# board.net
KiCad netlist of a schematic drawn in EAGLE
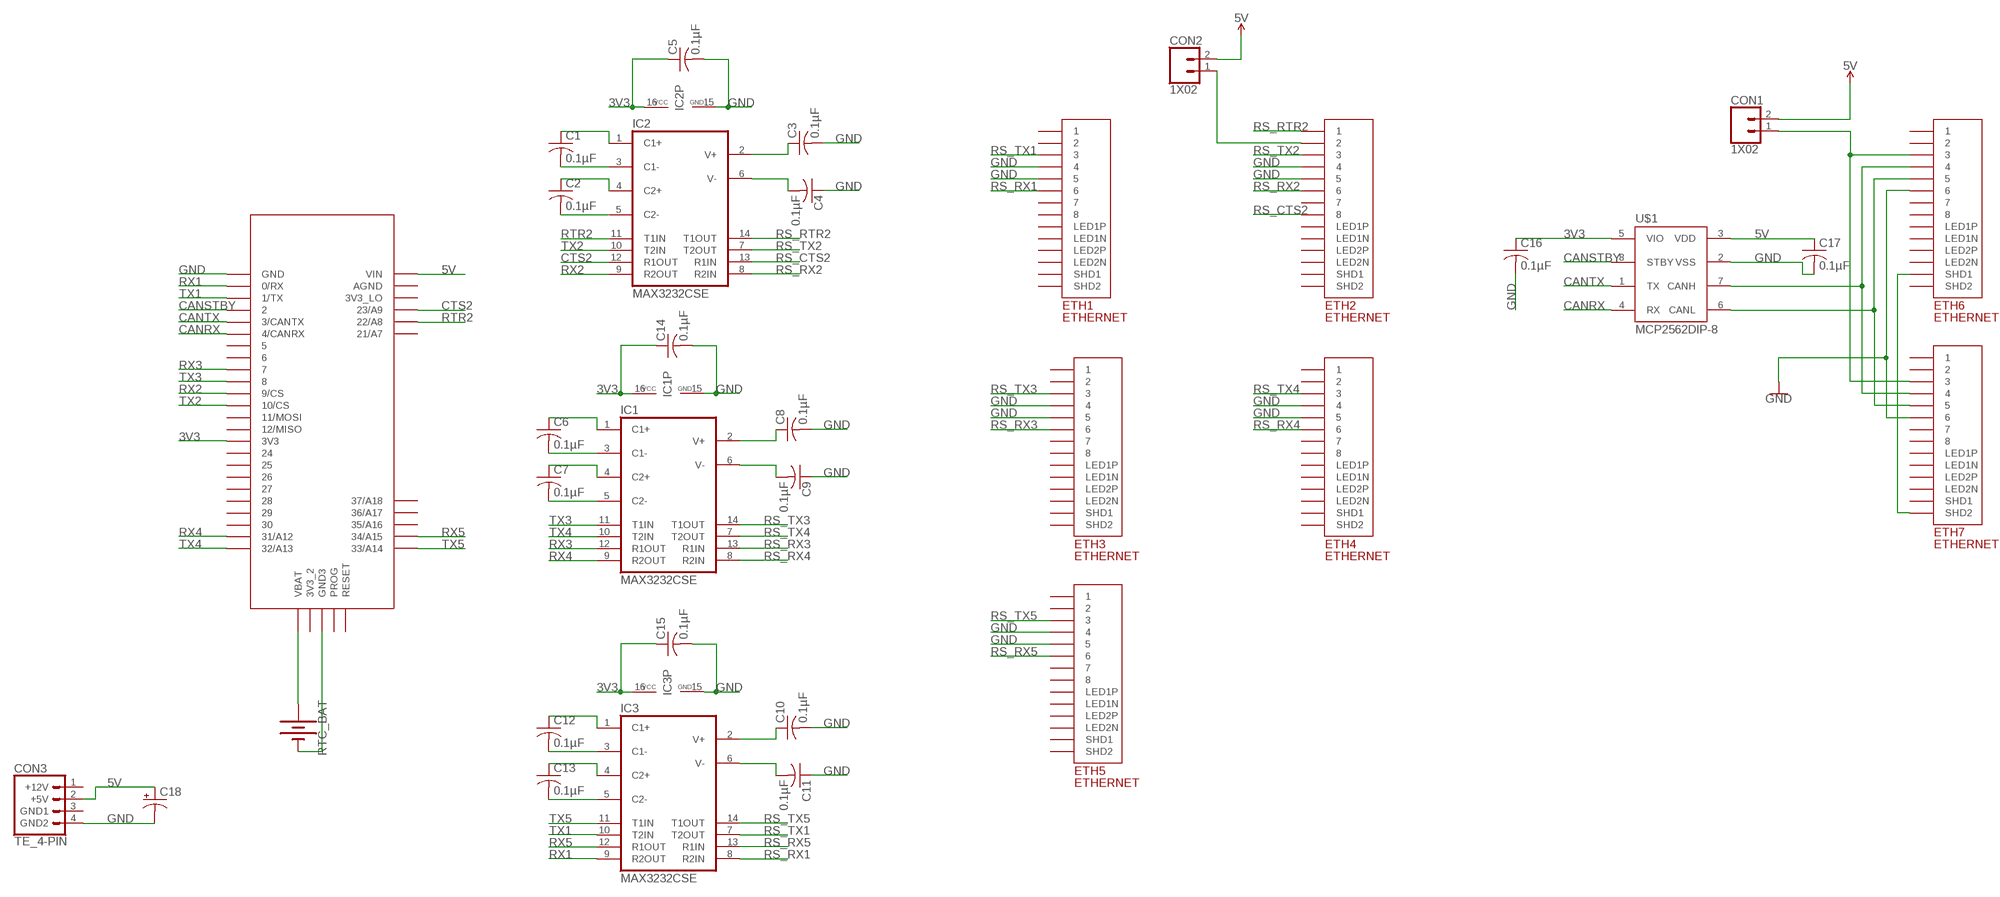
[diagram p0: schematic, sheet 1]

(export (version "E")
  (design (tool "Eeschema 10.0.6"))
  (components
    (comp (ref "C1")
      (value "0.1µF")
      (footprint "eagle-import:C0805")
      (libsource (lib "eagle-import") (part "C-USC0805"))
    )
    (comp (ref "C2")
      (value "0.1µF")
      (footprint "eagle-import:C0805")
      (libsource (lib "eagle-import") (part "C-USC0805"))
    )
    (comp (ref "C3")
      (value "0.1µF")
      (footprint "eagle-import:C0805")
      (libsource (lib "eagle-import") (part "C-USC0805"))
    )
    (comp (ref "C4")
      (value "0.1µF")
      (footprint "eagle-import:C0805")
      (libsource (lib "eagle-import") (part "C-USC0805"))
    )
    (comp (ref "C5")
      (value "0.1µF")
      (footprint "eagle-import:C0805")
      (libsource (lib "eagle-import") (part "C-USC0805"))
    )
    (comp (ref "C6")
      (value "0.1µF")
      (footprint "eagle-import:C0805")
      (libsource (lib "eagle-import") (part "C-USC0805"))
    )
    (comp (ref "C7")
      (value "0.1µF")
      (footprint "eagle-import:C0805")
      (libsource (lib "eagle-import") (part "C-USC0805"))
    )
    (comp (ref "C8")
      (value "0.1µF")
      (footprint "eagle-import:C0805")
      (libsource (lib "eagle-import") (part "C-USC0805"))
    )
    (comp (ref "C9")
      (value "0.1µF")
      (footprint "eagle-import:C0805")
      (libsource (lib "eagle-import") (part "C-USC0805"))
    )
    (comp (ref "C10")
      (value "0.1µF")
      (footprint "eagle-import:C0805")
      (libsource (lib "eagle-import") (part "C-USC0805"))
    )
    (comp (ref "C11")
      (value "0.1µF")
      (footprint "eagle-import:C0805")
      (libsource (lib "eagle-import") (part "C-USC0805"))
    )
    (comp (ref "C12")
      (value "0.1µF")
      (footprint "eagle-import:C0805")
      (libsource (lib "eagle-import") (part "C-USC0805"))
    )
    (comp (ref "C13")
      (value "0.1µF")
      (footprint "eagle-import:C0805")
      (libsource (lib "eagle-import") (part "C-USC0805"))
    )
    (comp (ref "C14")
      (value "0.1µF")
      (footprint "eagle-import:C0805")
      (libsource (lib "eagle-import") (part "C-USC0805"))
    )
    (comp (ref "C15")
      (value "0.1µF")
      (footprint "eagle-import:C0805")
      (libsource (lib "eagle-import") (part "C-USC0805"))
    )
    (comp (ref "C16")
      (value "0.1µF")
      (footprint "eagle-import:C0805")
      (libsource (lib "eagle-import") (part "C-USC0805"))
    )
    (comp (ref "C17")
      (value "0.1µF")
      (footprint "eagle-import:C0805")
      (libsource (lib "eagle-import") (part "C-USC0805"))
    )
    (comp (ref "C18")
      (value "CAPACITOR_ELECTROLYTIC_100UF")
      (footprint "eagle-import:CAPACITOR_100UF_50V")
      (libsource (lib "eagle-import") (part "CAPACITOR_ELECTROLYTIC_100UF"))
    )
    (comp (ref "CON1")
      (value "1X02")
      (footprint "eagle-import:1X02")
      (libsource (lib "eagle-import") (part "1X02"))
    )
    (comp (ref "CON2")
      (value "1X02")
      (footprint "eagle-import:1X02")
      (libsource (lib "eagle-import") (part "1X02"))
    )
    (comp (ref "CON3")
      (value "TE_4-PIN")
      (footprint "eagle-import:TE_4-PIN")
      (libsource (lib "eagle-import") (part "TE_4-PIN"))
    )
    (comp (ref "ETH1")
      (value "ETHERNET")
      (footprint "eagle-import:A122645-ND")
      (libsource (lib "eagle-import") (part "ETHERNET"))
    )
    (comp (ref "ETH2")
      (value "ETHERNET")
      (footprint "eagle-import:A122645-ND")
      (libsource (lib "eagle-import") (part "ETHERNET"))
    )
    (comp (ref "ETH3")
      (value "ETHERNET")
      (footprint "eagle-import:A122645-ND")
      (libsource (lib "eagle-import") (part "ETHERNET"))
    )
    (comp (ref "ETH4")
      (value "ETHERNET")
      (footprint "eagle-import:A122645-ND")
      (libsource (lib "eagle-import") (part "ETHERNET"))
    )
    (comp (ref "ETH5")
      (value "ETHERNET")
      (footprint "eagle-import:A122645-ND")
      (libsource (lib "eagle-import") (part "ETHERNET"))
    )
    (comp (ref "ETH6")
      (value "ETHERNET")
      (footprint "eagle-import:A122645-ND")
      (libsource (lib "eagle-import") (part "ETHERNET"))
    )
    (comp (ref "ETH7")
      (value "ETHERNET")
      (footprint "eagle-import:A122645-ND")
      (libsource (lib "eagle-import") (part "ETHERNET"))
    )
    (comp (ref "IC1")
      (value "MAX3232CSE")
      (footprint "eagle-import:SO16")
      (libsource (lib "eagle-import") (part "MAX3232SEC"))
    )
    (comp (ref "IC2")
      (value "MAX3232CSE")
      (footprint "eagle-import:SO16")
      (libsource (lib "eagle-import") (part "MAX3232SEC"))
    )
    (comp (ref "IC3")
      (value "MAX3232CSE")
      (footprint "eagle-import:SO16")
      (libsource (lib "eagle-import") (part "MAX3232SEC"))
    )
    (comp (ref "RTC_BAT")
      (value "BATTERY-20MM_PTH")
      (footprint "eagle-import:BATTCOM_20MM_PTH")
      (libsource (lib "eagle-import") (part "BATTERY-20MM_PTH"))
    )
    (comp (ref "U$1")
      (value "MCP2562DIP-8")
      (footprint "eagle-import:DIL08")
      (libsource (lib "eagle-import") (part "MCP2562DIP-8"))
    )
    (comp (ref "U$3")
      (value "TEENSY_3.5/3.6_NOPAD")
      (footprint "eagle-import:TEENSY_3.5_3.6_NOPAD")
      (libsource (lib "eagle-import") (part "TEENSY_3.5/3.6_NOPAD"))
    )
  )
  (nets
    (net (code "1") (name "/3V3") (class "Default")
      (node (ref "C14") (pin "1") (pinfunction "1_1") (pintype "passive"))
      (node (ref "C15") (pin "1") (pinfunction "1_1") (pintype "passive"))
      (node (ref "C16") (pin "1") (pinfunction "1_1") (pintype "passive"))
      (node (ref "C5") (pin "1") (pinfunction "1_1") (pintype "passive"))
      (node (ref "IC1") (pin "16") (pinfunction "VCC_16") (pintype "power_in"))
      (node (ref "IC2") (pin "16") (pinfunction "VCC_16") (pintype "power_in"))
      (node (ref "IC3") (pin "16") (pinfunction "VCC_16") (pintype "power_in"))
      (node (ref "U$1") (pin "5") (pinfunction "VIO_5") (pintype "bidirectional"))
      (node (ref "U$3") (pin "3V3") (pinfunction "3V3_3V3") (pintype "bidirectional"))
    )
    (net (code "2") (name "/CANRX") (class "Default")
      (node (ref "U$1") (pin "4") (pinfunction "RX_4") (pintype "bidirectional"))
      (node (ref "U$3") (pin "4/CANRX") (pinfunction "4/CANRX_4/CANRX") (pintype "bidirectional"))
    )
    (net (code "3") (name "/CANSTBY") (class "Default")
      (node (ref "U$1") (pin "8") (pinfunction "STBY_8") (pintype "bidirectional"))
      (node (ref "U$3") (pin "2") (pinfunction "2_2") (pintype "bidirectional"))
    )
    (net (code "4") (name "/CANTX") (class "Default")
      (node (ref "U$1") (pin "1") (pinfunction "TX_1") (pintype "bidirectional"))
      (node (ref "U$3") (pin "3/CANTX") (pinfunction "3/CANTX_3/CANTX") (pintype "bidirectional"))
    )
    (net (code "5") (name "/CTS2") (class "Default")
      (node (ref "IC2") (pin "12") (pinfunction "R1OUT_12") (pintype "output"))
      (node (ref "U$3") (pin "23/A9") (pinfunction "23/A9_23/A9") (pintype "bidirectional"))
    )
    (net (code "6") (name "/RS_CTS2") (class "Default")
      (node (ref "ETH2") (pin "P$8") (pinfunction "8_P$8") (pintype "bidirectional"))
      (node (ref "IC2") (pin "13") (pinfunction "R1IN_13") (pintype "input"))
    )
    (net (code "7") (name "/RS_RTR2") (class "Default")
      (node (ref "ETH2") (pin "P$1") (pinfunction "1_P$1") (pintype "bidirectional"))
      (node (ref "IC2") (pin "14") (pinfunction "T1OUT_14") (pintype "output"))
    )
    (net (code "8") (name "/RS_RX1") (class "Default")
      (node (ref "ETH1") (pin "P$6") (pinfunction "6_P$6") (pintype "bidirectional"))
      (node (ref "IC3") (pin "8") (pinfunction "R2IN_8") (pintype "input"))
    )
    (net (code "9") (name "/RS_RX2") (class "Default")
      (node (ref "ETH2") (pin "P$6") (pinfunction "6_P$6") (pintype "bidirectional"))
      (node (ref "IC2") (pin "8") (pinfunction "R2IN_8") (pintype "input"))
    )
    (net (code "10") (name "/RS_RX3") (class "Default")
      (node (ref "ETH3") (pin "P$6") (pinfunction "6_P$6") (pintype "bidirectional"))
      (node (ref "IC1") (pin "13") (pinfunction "R1IN_13") (pintype "input"))
    )
    (net (code "11") (name "/RS_RX4") (class "Default")
      (node (ref "ETH4") (pin "P$6") (pinfunction "6_P$6") (pintype "bidirectional"))
      (node (ref "IC1") (pin "8") (pinfunction "R2IN_8") (pintype "input"))
    )
    (net (code "12") (name "/RS_RX5") (class "Default")
      (node (ref "ETH5") (pin "P$6") (pinfunction "6_P$6") (pintype "bidirectional"))
      (node (ref "IC3") (pin "13") (pinfunction "R1IN_13") (pintype "input"))
    )
    (net (code "13") (name "/RS_TX1") (class "Default")
      (node (ref "ETH1") (pin "P$3") (pinfunction "3_P$3") (pintype "bidirectional"))
      (node (ref "IC3") (pin "7") (pinfunction "T2OUT_7") (pintype "output"))
    )
    (net (code "14") (name "/RS_TX2") (class "Default")
      (node (ref "ETH2") (pin "P$3") (pinfunction "3_P$3") (pintype "bidirectional"))
      (node (ref "IC2") (pin "7") (pinfunction "T2OUT_7") (pintype "output"))
    )
    (net (code "15") (name "/RS_TX3") (class "Default")
      (node (ref "ETH3") (pin "P$3") (pinfunction "3_P$3") (pintype "bidirectional"))
      (node (ref "IC1") (pin "14") (pinfunction "T1OUT_14") (pintype "output"))
    )
    (net (code "16") (name "/RS_TX4") (class "Default")
      (node (ref "ETH4") (pin "P$3") (pinfunction "3_P$3") (pintype "bidirectional"))
      (node (ref "IC1") (pin "7") (pinfunction "T2OUT_7") (pintype "output"))
    )
    (net (code "17") (name "/RS_TX5") (class "Default")
      (node (ref "ETH5") (pin "P$3") (pinfunction "3_P$3") (pintype "bidirectional"))
      (node (ref "IC3") (pin "14") (pinfunction "T1OUT_14") (pintype "output"))
    )
    (net (code "18") (name "/RTR2") (class "Default")
      (node (ref "IC2") (pin "11") (pinfunction "T1IN_11") (pintype "input"))
      (node (ref "U$3") (pin "22/A8") (pinfunction "22/A8_22/A8") (pintype "bidirectional"))
    )
    (net (code "19") (name "/RX1") (class "Default")
      (node (ref "IC3") (pin "9") (pinfunction "R2OUT_9") (pintype "output"))
      (node (ref "U$3") (pin "0/RX") (pinfunction "0/RX_0/RX") (pintype "bidirectional"))
    )
    (net (code "20") (name "/RX2") (class "Default")
      (node (ref "IC2") (pin "9") (pinfunction "R2OUT_9") (pintype "output"))
      (node (ref "U$3") (pin "9/CS") (pinfunction "9/CS_9/CS") (pintype "bidirectional"))
    )
    (net (code "21") (name "/RX3") (class "Default")
      (node (ref "IC1") (pin "12") (pinfunction "R1OUT_12") (pintype "output"))
      (node (ref "U$3") (pin "7") (pinfunction "7_7") (pintype "bidirectional"))
    )
    (net (code "22") (name "/RX4") (class "Default")
      (node (ref "IC1") (pin "9") (pinfunction "R2OUT_9") (pintype "output"))
      (node (ref "U$3") (pin "31/A12") (pinfunction "31/A12_31/A12") (pintype "bidirectional"))
    )
    (net (code "23") (name "/RX5") (class "Default")
      (node (ref "IC3") (pin "12") (pinfunction "R1OUT_12") (pintype "output"))
      (node (ref "U$3") (pin "34/A15") (pinfunction "34/A15_34/A15") (pintype "bidirectional"))
    )
    (net (code "24") (name "/TX1") (class "Default")
      (node (ref "IC3") (pin "10") (pinfunction "T2IN_10") (pintype "input"))
      (node (ref "U$3") (pin "1/TX") (pinfunction "1/TX_1/TX") (pintype "bidirectional"))
    )
    (net (code "25") (name "/TX2") (class "Default")
      (node (ref "IC2") (pin "10") (pinfunction "T2IN_10") (pintype "input"))
      (node (ref "U$3") (pin "10/CS") (pinfunction "10/CS_10/CS") (pintype "bidirectional"))
    )
    (net (code "26") (name "/TX3") (class "Default")
      (node (ref "IC1") (pin "11") (pinfunction "T1IN_11") (pintype "input"))
      (node (ref "U$3") (pin "8") (pinfunction "8_8") (pintype "bidirectional"))
    )
    (net (code "27") (name "/TX4") (class "Default")
      (node (ref "IC1") (pin "10") (pinfunction "T2IN_10") (pintype "input"))
      (node (ref "U$3") (pin "32/A13") (pinfunction "32/A13_32/A13") (pintype "bidirectional"))
    )
    (net (code "28") (name "/TX5") (class "Default")
      (node (ref "IC3") (pin "11") (pinfunction "T1IN_11") (pintype "input"))
      (node (ref "U$3") (pin "33/A14") (pinfunction "33/A14_33/A14") (pintype "bidirectional"))
    )
    (net (code "29") (name "5V") (class "Default")
      (node (ref "C17") (pin "1") (pinfunction "1_1") (pintype "passive"))
      (node (ref "C18") (pin "+") (pinfunction "+_+") (pintype "passive"))
      (node (ref "CON1") (pin "2") (pinfunction "2_2") (pintype "passive"))
      (node (ref "CON2") (pin "2") (pinfunction "2_2") (pintype "passive"))
      (node (ref "CON3") (pin "2") (pinfunction "+5V_2") (pintype "passive"))
      (node (ref "U$1") (pin "3") (pinfunction "VDD_3") (pintype "bidirectional"))
      (node (ref "U$3") (pin "VIN") (pinfunction "VIN_VIN") (pintype "bidirectional"))
    )
    (net (code "30") (name "GND") (class "Default")
      (node (ref "C10") (pin "2") (pinfunction "2_2") (pintype "passive"))
      (node (ref "C11") (pin "1") (pinfunction "1_1") (pintype "passive"))
      (node (ref "C14") (pin "2") (pinfunction "2_2") (pintype "passive"))
      (node (ref "C15") (pin "2") (pinfunction "2_2") (pintype "passive"))
      (node (ref "C16") (pin "2") (pinfunction "2_2") (pintype "passive"))
      (node (ref "C17") (pin "2") (pinfunction "2_2") (pintype "passive"))
      (node (ref "C18") (pin "-") (pinfunction "-_-") (pintype "passive"))
      (node (ref "C3") (pin "2") (pinfunction "2_2") (pintype "passive"))
      (node (ref "C4") (pin "1") (pinfunction "1_1") (pintype "passive"))
      (node (ref "C5") (pin "2") (pinfunction "2_2") (pintype "passive"))
      (node (ref "C8") (pin "2") (pinfunction "2_2") (pintype "passive"))
      (node (ref "C9") (pin "1") (pinfunction "1_1") (pintype "passive"))
      (node (ref "CON3") (pin "4") (pinfunction "GND2_4") (pintype "passive"))
      (node (ref "ETH1") (pin "P$4") (pinfunction "4_P$4") (pintype "bidirectional"))
      (node (ref "ETH1") (pin "P$5") (pinfunction "5_P$5") (pintype "bidirectional"))
      (node (ref "ETH2") (pin "P$4") (pinfunction "4_P$4") (pintype "bidirectional"))
      (node (ref "ETH2") (pin "P$5") (pinfunction "5_P$5") (pintype "bidirectional"))
      (node (ref "ETH3") (pin "P$4") (pinfunction "4_P$4") (pintype "bidirectional"))
      (node (ref "ETH3") (pin "P$5") (pinfunction "5_P$5") (pintype "bidirectional"))
      (node (ref "ETH4") (pin "P$4") (pinfunction "4_P$4") (pintype "bidirectional"))
      (node (ref "ETH4") (pin "P$5") (pinfunction "5_P$5") (pintype "bidirectional"))
      (node (ref "ETH5") (pin "P$4") (pinfunction "4_P$4") (pintype "bidirectional"))
      (node (ref "ETH5") (pin "P$5") (pinfunction "5_P$5") (pintype "bidirectional"))
      (node (ref "ETH6") (pin "P$6") (pinfunction "6_P$6") (pintype "bidirectional"))
      (node (ref "ETH7") (pin "P$6") (pinfunction "6_P$6") (pintype "bidirectional"))
      (node (ref "IC1") (pin "15") (pinfunction "GND_15") (pintype "power_in"))
      (node (ref "IC2") (pin "15") (pinfunction "GND_15") (pintype "power_in"))
      (node (ref "IC3") (pin "15") (pinfunction "GND_15") (pintype "power_in"))
      (node (ref "U$1") (pin "2") (pinfunction "VSS_2") (pintype "bidirectional"))
      (node (ref "U$3") (pin "GND") (pinfunction "GND_GND") (pintype "bidirectional"))
    )
    (net (code "31") (name "Net-(ETH2-2)") (class "Default")
      (node (ref "CON2") (pin "1") (pinfunction "1_1") (pintype "passive"))
      (node (ref "ETH2") (pin "P$2") (pinfunction "2_P$2") (pintype "bidirectional"))
    )
    (net (code "32") (name "Net-(ETH6-3)") (class "Default")
      (node (ref "CON1") (pin "1") (pinfunction "1_1") (pintype "passive"))
      (node (ref "ETH6") (pin "P$3") (pinfunction "3_P$3") (pintype "bidirectional"))
      (node (ref "ETH7") (pin "P$3") (pinfunction "3_P$3") (pintype "bidirectional"))
    )
    (net (code "33") (name "Net-(ETH6-4)") (class "Default")
      (node (ref "ETH6") (pin "P$4") (pinfunction "4_P$4") (pintype "bidirectional"))
      (node (ref "ETH7") (pin "P$4") (pinfunction "4_P$4") (pintype "bidirectional"))
      (node (ref "U$1") (pin "7") (pinfunction "CANH_7") (pintype "bidirectional"))
    )
    (net (code "34") (name "Net-(ETH6-5)") (class "Default")
      (node (ref "ETH6") (pin "P$5") (pinfunction "5_P$5") (pintype "bidirectional"))
      (node (ref "ETH7") (pin "P$5") (pinfunction "5_P$5") (pintype "bidirectional"))
      (node (ref "U$1") (pin "6") (pinfunction "CANL_6") (pintype "bidirectional"))
    )
    (net (code "35") (name "Net-(ETH6-SHD1)") (class "Default")
      (node (ref "ETH6") (pin "P$13") (pinfunction "SHD1_P$13") (pintype "bidirectional"))
      (node (ref "ETH7") (pin "P$14") (pinfunction "SHD2_P$14") (pintype "bidirectional"))
    )
    (net (code "36") (name "Net-(IC1A-C1+)") (class "Default")
      (node (ref "C6") (pin "1") (pinfunction "1_1") (pintype "passive"))
      (node (ref "IC1") (pin "1") (pinfunction "C1+_1") (pintype "bidirectional"))
    )
    (net (code "37") (name "Net-(IC1A-C1-)") (class "Default")
      (node (ref "C6") (pin "2") (pinfunction "2_2") (pintype "passive"))
      (node (ref "IC1") (pin "3") (pinfunction "C1-_3") (pintype "bidirectional"))
    )
    (net (code "38") (name "Net-(IC1A-C2+)") (class "Default")
      (node (ref "C7") (pin "1") (pinfunction "1_1") (pintype "passive"))
      (node (ref "IC1") (pin "4") (pinfunction "C2+_4") (pintype "bidirectional"))
    )
    (net (code "39") (name "Net-(IC1A-C2-)") (class "Default")
      (node (ref "C7") (pin "2") (pinfunction "2_2") (pintype "passive"))
      (node (ref "IC1") (pin "5") (pinfunction "C2-_5") (pintype "bidirectional"))
    )
    (net (code "40") (name "Net-(IC1A-V+)") (class "Default")
      (node (ref "C8") (pin "1") (pinfunction "1_1") (pintype "passive"))
      (node (ref "IC1") (pin "2") (pinfunction "V+_2") (pintype "bidirectional"))
    )
    (net (code "41") (name "Net-(IC1A-V-)") (class "Default")
      (node (ref "C9") (pin "2") (pinfunction "2_2") (pintype "passive"))
      (node (ref "IC1") (pin "6") (pinfunction "V-_6") (pintype "bidirectional"))
    )
    (net (code "42") (name "Net-(IC2A-C1+)") (class "Default")
      (node (ref "C1") (pin "1") (pinfunction "1_1") (pintype "passive"))
      (node (ref "IC2") (pin "1") (pinfunction "C1+_1") (pintype "bidirectional"))
    )
    (net (code "43") (name "Net-(IC2A-C1-)") (class "Default")
      (node (ref "C1") (pin "2") (pinfunction "2_2") (pintype "passive"))
      (node (ref "IC2") (pin "3") (pinfunction "C1-_3") (pintype "bidirectional"))
    )
    (net (code "44") (name "Net-(IC2A-C2+)") (class "Default")
      (node (ref "C2") (pin "1") (pinfunction "1_1") (pintype "passive"))
      (node (ref "IC2") (pin "4") (pinfunction "C2+_4") (pintype "bidirectional"))
    )
    (net (code "45") (name "Net-(IC2A-C2-)") (class "Default")
      (node (ref "C2") (pin "2") (pinfunction "2_2") (pintype "passive"))
      (node (ref "IC2") (pin "5") (pinfunction "C2-_5") (pintype "bidirectional"))
    )
    (net (code "46") (name "Net-(IC2A-V+)") (class "Default")
      (node (ref "C3") (pin "1") (pinfunction "1_1") (pintype "passive"))
      (node (ref "IC2") (pin "2") (pinfunction "V+_2") (pintype "bidirectional"))
    )
    (net (code "47") (name "Net-(IC2A-V-)") (class "Default")
      (node (ref "C4") (pin "2") (pinfunction "2_2") (pintype "passive"))
      (node (ref "IC2") (pin "6") (pinfunction "V-_6") (pintype "bidirectional"))
    )
    (net (code "48") (name "Net-(IC3A-C1+)") (class "Default")
      (node (ref "C12") (pin "1") (pinfunction "1_1") (pintype "passive"))
      (node (ref "IC3") (pin "1") (pinfunction "C1+_1") (pintype "bidirectional"))
    )
    (net (code "49") (name "Net-(IC3A-C1-)") (class "Default")
      (node (ref "C12") (pin "2") (pinfunction "2_2") (pintype "passive"))
      (node (ref "IC3") (pin "3") (pinfunction "C1-_3") (pintype "bidirectional"))
    )
    (net (code "50") (name "Net-(IC3A-C2+)") (class "Default")
      (node (ref "C13") (pin "1") (pinfunction "1_1") (pintype "passive"))
      (node (ref "IC3") (pin "4") (pinfunction "C2+_4") (pintype "bidirectional"))
    )
    (net (code "51") (name "Net-(IC3A-C2-)") (class "Default")
      (node (ref "C13") (pin "2") (pinfunction "2_2") (pintype "passive"))
      (node (ref "IC3") (pin "5") (pinfunction "C2-_5") (pintype "bidirectional"))
    )
    (net (code "52") (name "Net-(IC3A-V+)") (class "Default")
      (node (ref "C10") (pin "1") (pinfunction "1_1") (pintype "passive"))
      (node (ref "IC3") (pin "2") (pinfunction "V+_2") (pintype "bidirectional"))
    )
    (net (code "53") (name "Net-(IC3A-V-)") (class "Default")
      (node (ref "C11") (pin "2") (pinfunction "2_2") (pintype "passive"))
      (node (ref "IC3") (pin "6") (pinfunction "V-_6") (pintype "bidirectional"))
    )
    (net (code "54") (name "Net-(RTC_BAT-+)") (class "Default")
      (node (ref "RTC_BAT") (pin "1") (pinfunction "+_1") (pintype "power_in"))
      (node (ref "U$3") (pin "VBAT") (pinfunction "VBAT_VBAT") (pintype "bidirectional"))
    )
    (net (code "55") (name "Net-(RTC_BAT--)") (class "Default")
      (node (ref "RTC_BAT") (pin "2") (pinfunction "-_2") (pintype "power_in"))
      (node (ref "U$3") (pin "GND3") (pinfunction "GND3_GND3") (pintype "bidirectional"))
    )
    (net (code "56") (name "unconnected-(CON3-+12V-Pad1)") (class "Default")
      (node (ref "CON3") (pin "1") (pinfunction "+12V_1") (pintype "passive"))
    )
    (net (code "57") (name "unconnected-(CON3-GND1-Pad3)") (class "Default")
      (node (ref "CON3") (pin "3") (pinfunction "GND1_3") (pintype "passive"))
    )
    (net (code "58") (name "unconnected-(ETH1-1-PadP$1)") (class "Default")
      (node (ref "ETH1") (pin "P$1") (pinfunction "1_P$1") (pintype "bidirectional"))
    )
    (net (code "59") (name "unconnected-(ETH1-2-PadP$2)") (class "Default")
      (node (ref "ETH1") (pin "P$2") (pinfunction "2_P$2") (pintype "bidirectional"))
    )
    (net (code "60") (name "unconnected-(ETH1-7-PadP$7)") (class "Default")
      (node (ref "ETH1") (pin "P$7") (pinfunction "7_P$7") (pintype "bidirectional"))
    )
    (net (code "61") (name "unconnected-(ETH1-8-PadP$8)") (class "Default")
      (node (ref "ETH1") (pin "P$8") (pinfunction "8_P$8") (pintype "bidirectional"))
    )
    (net (code "62") (name "unconnected-(ETH1-LED1N-PadP$9)") (class "Default")
      (node (ref "ETH1") (pin "P$9") (pinfunction "LED1N_P$9") (pintype "bidirectional"))
    )
    (net (code "63") (name "unconnected-(ETH1-LED1P-PadP$10)") (class "Default")
      (node (ref "ETH1") (pin "P$10") (pinfunction "LED1P_P$10") (pintype "bidirectional"))
    )
    (net (code "64") (name "unconnected-(ETH1-LED2N-PadP$11)") (class "Default")
      (node (ref "ETH1") (pin "P$11") (pinfunction "LED2N_P$11") (pintype "bidirectional"))
    )
    (net (code "65") (name "unconnected-(ETH1-LED2P-PadP$12)") (class "Default")
      (node (ref "ETH1") (pin "P$12") (pinfunction "LED2P_P$12") (pintype "bidirectional"))
    )
    (net (code "66") (name "unconnected-(ETH1-SHD1-PadP$13)") (class "Default")
      (node (ref "ETH1") (pin "P$13") (pinfunction "SHD1_P$13") (pintype "bidirectional"))
    )
    (net (code "67") (name "unconnected-(ETH1-SHD2-PadP$14)") (class "Default")
      (node (ref "ETH1") (pin "P$14") (pinfunction "SHD2_P$14") (pintype "bidirectional"))
    )
    (net (code "68") (name "unconnected-(ETH2-7-PadP$7)") (class "Default")
      (node (ref "ETH2") (pin "P$7") (pinfunction "7_P$7") (pintype "bidirectional"))
    )
    (net (code "69") (name "unconnected-(ETH2-LED1N-PadP$9)") (class "Default")
      (node (ref "ETH2") (pin "P$9") (pinfunction "LED1N_P$9") (pintype "bidirectional"))
    )
    (net (code "70") (name "unconnected-(ETH2-LED1P-PadP$10)") (class "Default")
      (node (ref "ETH2") (pin "P$10") (pinfunction "LED1P_P$10") (pintype "bidirectional"))
    )
    (net (code "71") (name "unconnected-(ETH2-LED2N-PadP$11)") (class "Default")
      (node (ref "ETH2") (pin "P$11") (pinfunction "LED2N_P$11") (pintype "bidirectional"))
    )
    (net (code "72") (name "unconnected-(ETH2-LED2P-PadP$12)") (class "Default")
      (node (ref "ETH2") (pin "P$12") (pinfunction "LED2P_P$12") (pintype "bidirectional"))
    )
    (net (code "73") (name "unconnected-(ETH2-SHD1-PadP$13)") (class "Default")
      (node (ref "ETH2") (pin "P$13") (pinfunction "SHD1_P$13") (pintype "bidirectional"))
    )
    (net (code "74") (name "unconnected-(ETH2-SHD2-PadP$14)") (class "Default")
      (node (ref "ETH2") (pin "P$14") (pinfunction "SHD2_P$14") (pintype "bidirectional"))
    )
    (net (code "75") (name "unconnected-(ETH3-1-PadP$1)") (class "Default")
      (node (ref "ETH3") (pin "P$1") (pinfunction "1_P$1") (pintype "bidirectional"))
    )
    (net (code "76") (name "unconnected-(ETH3-2-PadP$2)") (class "Default")
      (node (ref "ETH3") (pin "P$2") (pinfunction "2_P$2") (pintype "bidirectional"))
    )
    (net (code "77") (name "unconnected-(ETH3-7-PadP$7)") (class "Default")
      (node (ref "ETH3") (pin "P$7") (pinfunction "7_P$7") (pintype "bidirectional"))
    )
    (net (code "78") (name "unconnected-(ETH3-8-PadP$8)") (class "Default")
      (node (ref "ETH3") (pin "P$8") (pinfunction "8_P$8") (pintype "bidirectional"))
    )
    (net (code "79") (name "unconnected-(ETH3-LED1N-PadP$9)") (class "Default")
      (node (ref "ETH3") (pin "P$9") (pinfunction "LED1N_P$9") (pintype "bidirectional"))
    )
    (net (code "80") (name "unconnected-(ETH3-LED1P-PadP$10)") (class "Default")
      (node (ref "ETH3") (pin "P$10") (pinfunction "LED1P_P$10") (pintype "bidirectional"))
    )
    (net (code "81") (name "unconnected-(ETH3-LED2N-PadP$11)") (class "Default")
      (node (ref "ETH3") (pin "P$11") (pinfunction "LED2N_P$11") (pintype "bidirectional"))
    )
    (net (code "82") (name "unconnected-(ETH3-LED2P-PadP$12)") (class "Default")
      (node (ref "ETH3") (pin "P$12") (pinfunction "LED2P_P$12") (pintype "bidirectional"))
    )
    (net (code "83") (name "unconnected-(ETH3-SHD1-PadP$13)") (class "Default")
      (node (ref "ETH3") (pin "P$13") (pinfunction "SHD1_P$13") (pintype "bidirectional"))
    )
    (net (code "84") (name "unconnected-(ETH3-SHD2-PadP$14)") (class "Default")
      (node (ref "ETH3") (pin "P$14") (pinfunction "SHD2_P$14") (pintype "bidirectional"))
    )
    (net (code "85") (name "unconnected-(ETH4-1-PadP$1)") (class "Default")
      (node (ref "ETH4") (pin "P$1") (pinfunction "1_P$1") (pintype "bidirectional"))
    )
    (net (code "86") (name "unconnected-(ETH4-2-PadP$2)") (class "Default")
      (node (ref "ETH4") (pin "P$2") (pinfunction "2_P$2") (pintype "bidirectional"))
    )
    (net (code "87") (name "unconnected-(ETH4-7-PadP$7)") (class "Default")
      (node (ref "ETH4") (pin "P$7") (pinfunction "7_P$7") (pintype "bidirectional"))
    )
    (net (code "88") (name "unconnected-(ETH4-8-PadP$8)") (class "Default")
      (node (ref "ETH4") (pin "P$8") (pinfunction "8_P$8") (pintype "bidirectional"))
    )
    (net (code "89") (name "unconnected-(ETH4-LED1N-PadP$9)") (class "Default")
      (node (ref "ETH4") (pin "P$9") (pinfunction "LED1N_P$9") (pintype "bidirectional"))
    )
    (net (code "90") (name "unconnected-(ETH4-LED1P-PadP$10)") (class "Default")
      (node (ref "ETH4") (pin "P$10") (pinfunction "LED1P_P$10") (pintype "bidirectional"))
    )
    (net (code "91") (name "unconnected-(ETH4-LED2N-PadP$11)") (class "Default")
      (node (ref "ETH4") (pin "P$11") (pinfunction "LED2N_P$11") (pintype "bidirectional"))
    )
    (net (code "92") (name "unconnected-(ETH4-LED2P-PadP$12)") (class "Default")
      (node (ref "ETH4") (pin "P$12") (pinfunction "LED2P_P$12") (pintype "bidirectional"))
    )
    (net (code "93") (name "unconnected-(ETH4-SHD1-PadP$13)") (class "Default")
      (node (ref "ETH4") (pin "P$13") (pinfunction "SHD1_P$13") (pintype "bidirectional"))
    )
    (net (code "94") (name "unconnected-(ETH4-SHD2-PadP$14)") (class "Default")
      (node (ref "ETH4") (pin "P$14") (pinfunction "SHD2_P$14") (pintype "bidirectional"))
    )
    (net (code "95") (name "unconnected-(ETH5-1-PadP$1)") (class "Default")
      (node (ref "ETH5") (pin "P$1") (pinfunction "1_P$1") (pintype "bidirectional"))
    )
    (net (code "96") (name "unconnected-(ETH5-2-PadP$2)") (class "Default")
      (node (ref "ETH5") (pin "P$2") (pinfunction "2_P$2") (pintype "bidirectional"))
    )
    (net (code "97") (name "unconnected-(ETH5-7-PadP$7)") (class "Default")
      (node (ref "ETH5") (pin "P$7") (pinfunction "7_P$7") (pintype "bidirectional"))
    )
    (net (code "98") (name "unconnected-(ETH5-8-PadP$8)") (class "Default")
      (node (ref "ETH5") (pin "P$8") (pinfunction "8_P$8") (pintype "bidirectional"))
    )
    (net (code "99") (name "unconnected-(ETH5-LED1N-PadP$9)") (class "Default")
      (node (ref "ETH5") (pin "P$9") (pinfunction "LED1N_P$9") (pintype "bidirectional"))
    )
    (net (code "100") (name "unconnected-(ETH5-LED1P-PadP$10)") (class "Default")
      (node (ref "ETH5") (pin "P$10") (pinfunction "LED1P_P$10") (pintype "bidirectional"))
    )
    (net (code "101") (name "unconnected-(ETH5-LED2N-PadP$11)") (class "Default")
      (node (ref "ETH5") (pin "P$11") (pinfunction "LED2N_P$11") (pintype "bidirectional"))
    )
    (net (code "102") (name "unconnected-(ETH5-LED2P-PadP$12)") (class "Default")
      (node (ref "ETH5") (pin "P$12") (pinfunction "LED2P_P$12") (pintype "bidirectional"))
    )
    (net (code "103") (name "unconnected-(ETH5-SHD1-PadP$13)") (class "Default")
      (node (ref "ETH5") (pin "P$13") (pinfunction "SHD1_P$13") (pintype "bidirectional"))
    )
    (net (code "104") (name "unconnected-(ETH5-SHD2-PadP$14)") (class "Default")
      (node (ref "ETH5") (pin "P$14") (pinfunction "SHD2_P$14") (pintype "bidirectional"))
    )
    (net (code "105") (name "unconnected-(ETH6-1-PadP$1)") (class "Default")
      (node (ref "ETH6") (pin "P$1") (pinfunction "1_P$1") (pintype "bidirectional"))
    )
    (net (code "106") (name "unconnected-(ETH6-2-PadP$2)") (class "Default")
      (node (ref "ETH6") (pin "P$2") (pinfunction "2_P$2") (pintype "bidirectional"))
    )
    (net (code "107") (name "unconnected-(ETH6-7-PadP$7)") (class "Default")
      (node (ref "ETH6") (pin "P$7") (pinfunction "7_P$7") (pintype "bidirectional"))
    )
    (net (code "108") (name "unconnected-(ETH6-8-PadP$8)") (class "Default")
      (node (ref "ETH6") (pin "P$8") (pinfunction "8_P$8") (pintype "bidirectional"))
    )
    (net (code "109") (name "unconnected-(ETH6-LED1N-PadP$9)") (class "Default")
      (node (ref "ETH6") (pin "P$9") (pinfunction "LED1N_P$9") (pintype "bidirectional"))
    )
    (net (code "110") (name "unconnected-(ETH6-LED1P-PadP$10)") (class "Default")
      (node (ref "ETH6") (pin "P$10") (pinfunction "LED1P_P$10") (pintype "bidirectional"))
    )
    (net (code "111") (name "unconnected-(ETH6-LED2N-PadP$11)") (class "Default")
      (node (ref "ETH6") (pin "P$11") (pinfunction "LED2N_P$11") (pintype "bidirectional"))
    )
    (net (code "112") (name "unconnected-(ETH6-LED2P-PadP$12)") (class "Default")
      (node (ref "ETH6") (pin "P$12") (pinfunction "LED2P_P$12") (pintype "bidirectional"))
    )
    (net (code "113") (name "unconnected-(ETH6-SHD2-PadP$14)") (class "Default")
      (node (ref "ETH6") (pin "P$14") (pinfunction "SHD2_P$14") (pintype "bidirectional"))
    )
    (net (code "114") (name "unconnected-(ETH7-1-PadP$1)") (class "Default")
      (node (ref "ETH7") (pin "P$1") (pinfunction "1_P$1") (pintype "bidirectional"))
    )
    (net (code "115") (name "unconnected-(ETH7-2-PadP$2)") (class "Default")
      (node (ref "ETH7") (pin "P$2") (pinfunction "2_P$2") (pintype "bidirectional"))
    )
    (net (code "116") (name "unconnected-(ETH7-7-PadP$7)") (class "Default")
      (node (ref "ETH7") (pin "P$7") (pinfunction "7_P$7") (pintype "bidirectional"))
    )
    (net (code "117") (name "unconnected-(ETH7-8-PadP$8)") (class "Default")
      (node (ref "ETH7") (pin "P$8") (pinfunction "8_P$8") (pintype "bidirectional"))
    )
    (net (code "118") (name "unconnected-(ETH7-LED1N-PadP$9)") (class "Default")
      (node (ref "ETH7") (pin "P$9") (pinfunction "LED1N_P$9") (pintype "bidirectional"))
    )
    (net (code "119") (name "unconnected-(ETH7-LED1P-PadP$10)") (class "Default")
      (node (ref "ETH7") (pin "P$10") (pinfunction "LED1P_P$10") (pintype "bidirectional"))
    )
    (net (code "120") (name "unconnected-(ETH7-LED2N-PadP$11)") (class "Default")
      (node (ref "ETH7") (pin "P$11") (pinfunction "LED2N_P$11") (pintype "bidirectional"))
    )
    (net (code "121") (name "unconnected-(ETH7-LED2P-PadP$12)") (class "Default")
      (node (ref "ETH7") (pin "P$12") (pinfunction "LED2P_P$12") (pintype "bidirectional"))
    )
    (net (code "122") (name "unconnected-(ETH7-SHD1-PadP$13)") (class "Default")
      (node (ref "ETH7") (pin "P$13") (pinfunction "SHD1_P$13") (pintype "bidirectional"))
    )
    (net (code "123") (name "unconnected-(U$3-Pad3V3_2)") (class "Default")
      (node (ref "U$3") (pin "3V3_2") (pinfunction "3V3_2_3V3_2") (pintype "bidirectional"))
    )
    (net (code "124") (name "unconnected-(U$3-Pad3V3_LO)") (class "Default")
      (node (ref "U$3") (pin "3V3_LO") (pinfunction "3V3_LO_3V3_LO") (pintype "bidirectional"))
    )
    (net (code "125") (name "unconnected-(U$3-Pad5)") (class "Default")
      (node (ref "U$3") (pin "5") (pinfunction "5_5") (pintype "bidirectional"))
    )
    (net (code "126") (name "unconnected-(U$3-Pad6)") (class "Default")
      (node (ref "U$3") (pin "6") (pinfunction "6_6") (pintype "bidirectional"))
    )
    (net (code "127") (name "unconnected-(U$3-Pad11{slash}MOSI)") (class "Default")
      (node (ref "U$3") (pin "11/MOSI") (pinfunction "11/MOSI_11/MOSI") (pintype "bidirectional"))
    )
    (net (code "128") (name "unconnected-(U$3-Pad12{slash}MISO)") (class "Default")
      (node (ref "U$3") (pin "12/MISO") (pinfunction "12/MISO_12/MISO") (pintype "bidirectional"))
    )
    (net (code "129") (name "unconnected-(U$3-Pad21{slash}A7)") (class "Default")
      (node (ref "U$3") (pin "21/A7") (pinfunction "21/A7_21/A7") (pintype "bidirectional"))
    )
    (net (code "130") (name "unconnected-(U$3-Pad24)") (class "Default")
      (node (ref "U$3") (pin "24") (pinfunction "24_24") (pintype "bidirectional"))
    )
    (net (code "131") (name "unconnected-(U$3-Pad25)") (class "Default")
      (node (ref "U$3") (pin "25") (pinfunction "25_25") (pintype "bidirectional"))
    )
    (net (code "132") (name "unconnected-(U$3-Pad26)") (class "Default")
      (node (ref "U$3") (pin "26") (pinfunction "26_26") (pintype "bidirectional"))
    )
    (net (code "133") (name "unconnected-(U$3-Pad27)") (class "Default")
      (node (ref "U$3") (pin "27") (pinfunction "27_27") (pintype "bidirectional"))
    )
    (net (code "134") (name "unconnected-(U$3-Pad28)") (class "Default")
      (node (ref "U$3") (pin "28") (pinfunction "28_28") (pintype "bidirectional"))
    )
    (net (code "135") (name "unconnected-(U$3-Pad29)") (class "Default")
      (node (ref "U$3") (pin "29") (pinfunction "29_29") (pintype "bidirectional"))
    )
    (net (code "136") (name "unconnected-(U$3-Pad30)") (class "Default")
      (node (ref "U$3") (pin "30") (pinfunction "30_30") (pintype "bidirectional"))
    )
    (net (code "137") (name "unconnected-(U$3-Pad35{slash}A16)") (class "Default")
      (node (ref "U$3") (pin "35/A16") (pinfunction "35/A16_35/A16") (pintype "bidirectional"))
    )
    (net (code "138") (name "unconnected-(U$3-Pad36{slash}A17)") (class "Default")
      (node (ref "U$3") (pin "36/A17") (pinfunction "36/A17_36/A17") (pintype "bidirectional"))
    )
    (net (code "139") (name "unconnected-(U$3-Pad37{slash}A18)") (class "Default")
      (node (ref "U$3") (pin "37/A18") (pinfunction "37/A18_37/A18") (pintype "bidirectional"))
    )
    (net (code "140") (name "unconnected-(U$3-PadAGND)") (class "Default")
      (node (ref "U$3") (pin "AGND") (pinfunction "AGND_AGND") (pintype "bidirectional"))
    )
    (net (code "141") (name "unconnected-(U$3-PadPROG)") (class "Default")
      (node (ref "U$3") (pin "PROG") (pinfunction "PROG_PROG") (pintype "bidirectional"))
    )
    (net (code "142") (name "unconnected-(U$3-PadRESET)") (class "Default")
      (node (ref "U$3") (pin "RESET") (pinfunction "RESET_RESET") (pintype "bidirectional"))
    )
  )
)
